# PID_heater.net
KiCad netlist of a schematic drawn in EAGLE
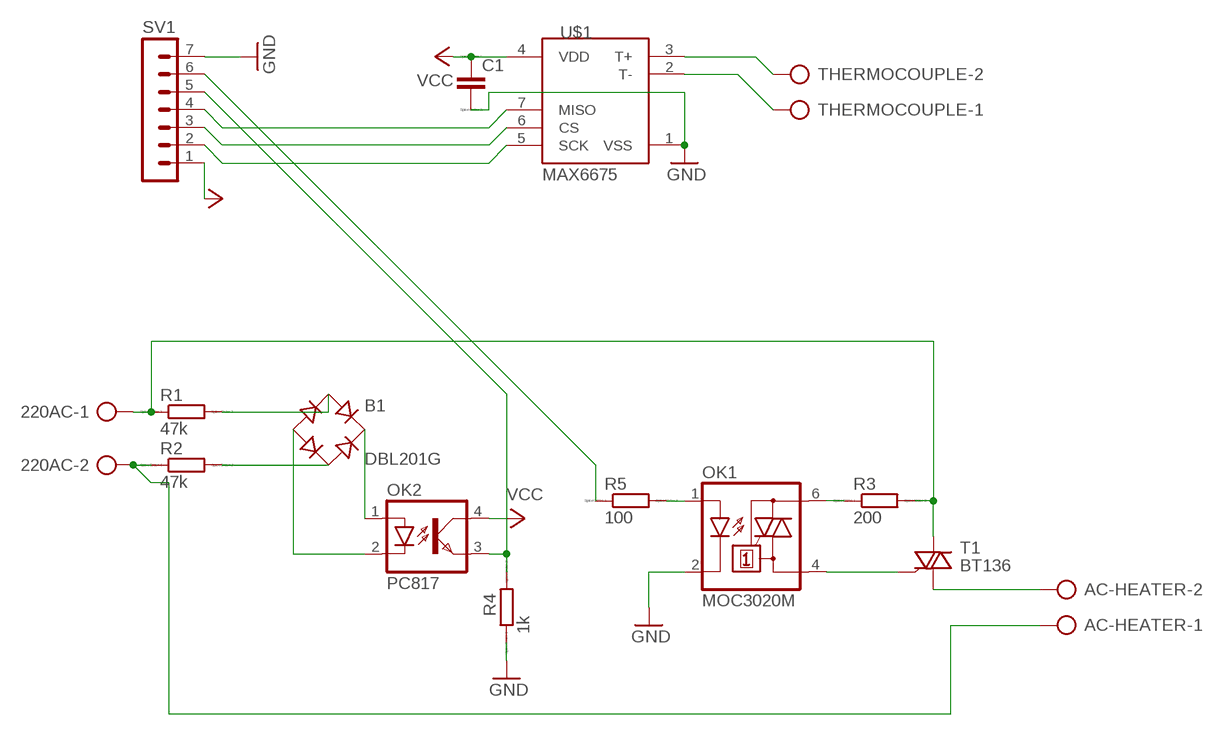
[diagram p0: schematic, sheet 1]

(export (version "E")
  (design (tool "Eeschema 10.0.6"))
  (components
    (comp (ref "220AC")
      (value "AK300/2")
      (footprint "eagle-import:AK300_2")
      (libsource (lib "eagle-import") (part "AK300/2"))
    )
    (comp (ref "AC-HEATER")
      (value "AK300/2")
      (footprint "eagle-import:AK300_2")
      (libsource (lib "eagle-import") (part "AK300/2"))
    )
    (comp (ref "B1")
      (value "DBL201G")
      (footprint "eagle-import:DB")
      (libsource (lib "eagle-import") (part "DB?GL201"))
    )
    (comp (ref "C1")
      (value "0.1u")
      (footprint "eagle-import:C0805")
      (libsource (lib "eagle-import") (part "C"))
    )
    (comp (ref "OK1")
      (value "MOC3020M")
      (footprint "eagle-import:DIL06")
      (fields (field (name "MF") "FAIRCHILD SEMICONDUCTOR") (field (name "MPN") "MOC3020-M"))
      (libsource (lib "eagle-import") (part "MOC30M20"))
    )
    (comp (ref "OK2")
      (value "PC817")
      (footprint "eagle-import:DIL04")
      (fields (field (name "MPN") "PC817X4J000F"))
      (libsource (lib "eagle-import") (part "PC817"))
    )
    (comp (ref "R1")
      (value "47k")
      (footprint "eagle-import:R0805")
      (libsource (lib "eagle-import") (part "R"))
    )
    (comp (ref "R2")
      (value "47k")
      (footprint "eagle-import:R0805")
      (libsource (lib "eagle-import") (part "R"))
    )
    (comp (ref "R3")
      (value "200")
      (footprint "eagle-import:R0805")
      (libsource (lib "eagle-import") (part "R"))
    )
    (comp (ref "R4")
      (value "1k")
      (footprint "eagle-import:R0805")
      (libsource (lib "eagle-import") (part "R"))
    )
    (comp (ref "R5")
      (value "100")
      (footprint "eagle-import:R0805")
      (libsource (lib "eagle-import") (part "R"))
    )
    (comp (ref "SV1")
      (value "MA07-1")
      (footprint "eagle-import:MA07-1")
      (libsource (lib "eagle-import") (part "MA07-1"))
    )
    (comp (ref "T1")
      (value "BT136")
      (footprint "eagle-import:TO220AB")
      (libsource (lib "eagle-import") (part "BT136"))
    )
    (comp (ref "THERMOCOUPLE")
      (value "AK300/2")
      (footprint "eagle-import:AK300_2")
      (libsource (lib "eagle-import") (part "AK300/2"))
    )
    (comp (ref "U$1")
      (value "MAX6675")
      (footprint "eagle-import:SO08")
      (libsource (lib "eagle-import") (part "MAX6675"))
    )
  )
  (nets
    (net (code "1") (name "GND") (class "Default")
      (node (ref "C1") (pin "2") (pinfunction "2_2") (pintype "passive"))
      (node (ref "OK1") (pin "2") (pinfunction "C_2") (pintype "passive"))
      (node (ref "R4") (pin "1") (pinfunction "1_1") (pintype "passive"))
      (node (ref "SV1") (pin "7") (pinfunction "7_7") (pintype "passive"))
      (node (ref "U$1") (pin "1") (pinfunction "VSS_1") (pintype "bidirectional"))
    )
    (net (code "2") (name "Net-(220ACA-KL)") (class "Default")
      (node (ref "220AC") (pin "1") (pinfunction "KL_1") (pintype "passive"))
      (node (ref "R1") (pin "1") (pinfunction "1_1") (pintype "passive"))
      (node (ref "R3") (pin "2") (pinfunction "2_2") (pintype "passive"))
      (node (ref "T1") (pin "2") (pinfunction "A2_2") (pintype "passive"))
    )
    (net (code "3") (name "Net-(220ACB-KL)") (class "Default")
      (node (ref "220AC") (pin "2") (pinfunction "KL_2") (pintype "passive"))
      (node (ref "AC-HEATER") (pin "1") (pinfunction "KL_1") (pintype "passive"))
      (node (ref "R2") (pin "1") (pinfunction "1_1") (pintype "passive"))
    )
    (net (code "4") (name "Net-(AC-HEATERB-KL)") (class "Default")
      (node (ref "AC-HEATER") (pin "2") (pinfunction "KL_2") (pintype "passive"))
      (node (ref "T1") (pin "1") (pinfunction "A1_1") (pintype "passive"))
    )
    (net (code "5") (name "Net-(B1-PadAC1)") (class "Default")
      (node (ref "B1") (pin "AC1") (pinfunction "AC1_AC1") (pintype "passive"))
      (node (ref "R1") (pin "2") (pinfunction "2_2") (pintype "passive"))
    )
    (net (code "6") (name "Net-(B1-PadAC2)") (class "Default")
      (node (ref "B1") (pin "AC2") (pinfunction "AC2_AC2") (pintype "passive"))
      (node (ref "R2") (pin "2") (pinfunction "2_2") (pintype "passive"))
    )
    (net (code "7") (name "Net-(OK1-A)") (class "Default")
      (node (ref "OK1") (pin "1") (pinfunction "A_1") (pintype "passive"))
      (node (ref "R5") (pin "2") (pinfunction "2_2") (pintype "passive"))
    )
    (net (code "8") (name "Net-(OK1-A1)") (class "Default")
      (node (ref "OK1") (pin "4") (pinfunction "A1_4") (pintype "passive"))
      (node (ref "T1") (pin "3") (pinfunction "G_3") (pintype "passive"))
    )
    (net (code "9") (name "Net-(OK1-A2)") (class "Default")
      (node (ref "OK1") (pin "6") (pinfunction "A2_6") (pintype "passive"))
      (node (ref "R3") (pin "1") (pinfunction "1_1") (pintype "passive"))
    )
    (net (code "10") (name "Net-(OK2-A)") (class "Default")
      (node (ref "B1") (pin "+") (pinfunction "+_+") (pintype "passive"))
      (node (ref "OK2") (pin "1") (pinfunction "A_1") (pintype "passive"))
    )
    (net (code "11") (name "Net-(OK2-C)") (class "Default")
      (node (ref "B1") (pin "-") (pinfunction "-_-") (pintype "passive"))
      (node (ref "OK2") (pin "2") (pinfunction "C_2") (pintype "passive"))
    )
    (net (code "12") (name "Net-(OK2-EMIT)") (class "Default")
      (node (ref "OK2") (pin "3") (pinfunction "EMIT_3") (pintype "passive"))
      (node (ref "R4") (pin "2") (pinfunction "2_2") (pintype "passive"))
      (node (ref "SV1") (pin "5") (pinfunction "5_5") (pintype "passive"))
    )
    (net (code "13") (name "Net-(R5-Pad1)") (class "Default")
      (node (ref "R5") (pin "1") (pinfunction "1_1") (pintype "passive"))
      (node (ref "SV1") (pin "6") (pinfunction "6_6") (pintype "passive"))
    )
    (net (code "14") (name "Net-(THERMOCOUPLEA-KL)") (class "Default")
      (node (ref "THERMOCOUPLE") (pin "1") (pinfunction "KL_1") (pintype "passive"))
      (node (ref "U$1") (pin "2") (pinfunction "T-_2") (pintype "bidirectional"))
    )
    (net (code "15") (name "Net-(THERMOCOUPLEB-KL)") (class "Default")
      (node (ref "THERMOCOUPLE") (pin "2") (pinfunction "KL_2") (pintype "passive"))
      (node (ref "U$1") (pin "3") (pinfunction "T+_3") (pintype "bidirectional"))
    )
    (net (code "16") (name "Net-(U$1-CS)") (class "Default")
      (node (ref "SV1") (pin "3") (pinfunction "3_3") (pintype "passive"))
      (node (ref "U$1") (pin "6") (pinfunction "CS_6") (pintype "bidirectional"))
    )
    (net (code "17") (name "Net-(U$1-MISO)") (class "Default")
      (node (ref "SV1") (pin "4") (pinfunction "4_4") (pintype "passive"))
      (node (ref "U$1") (pin "7") (pinfunction "MISO_7") (pintype "bidirectional"))
    )
    (net (code "18") (name "Net-(U$1-SCK)") (class "Default")
      (node (ref "SV1") (pin "2") (pinfunction "2_2") (pintype "passive"))
      (node (ref "U$1") (pin "5") (pinfunction "SCK_5") (pintype "bidirectional"))
    )
    (net (code "19") (name "VCC") (class "Default")
      (node (ref "C1") (pin "1") (pinfunction "1_1") (pintype "passive"))
      (node (ref "OK2") (pin "4") (pinfunction "COL_4") (pintype "passive"))
      (node (ref "SV1") (pin "1") (pinfunction "1_1") (pintype "passive"))
      (node (ref "U$1") (pin "4") (pinfunction "VDD_4") (pintype "bidirectional"))
    )
  )
)
